# devBoard.net
KiCad netlist of a schematic drawn in Altium Designer
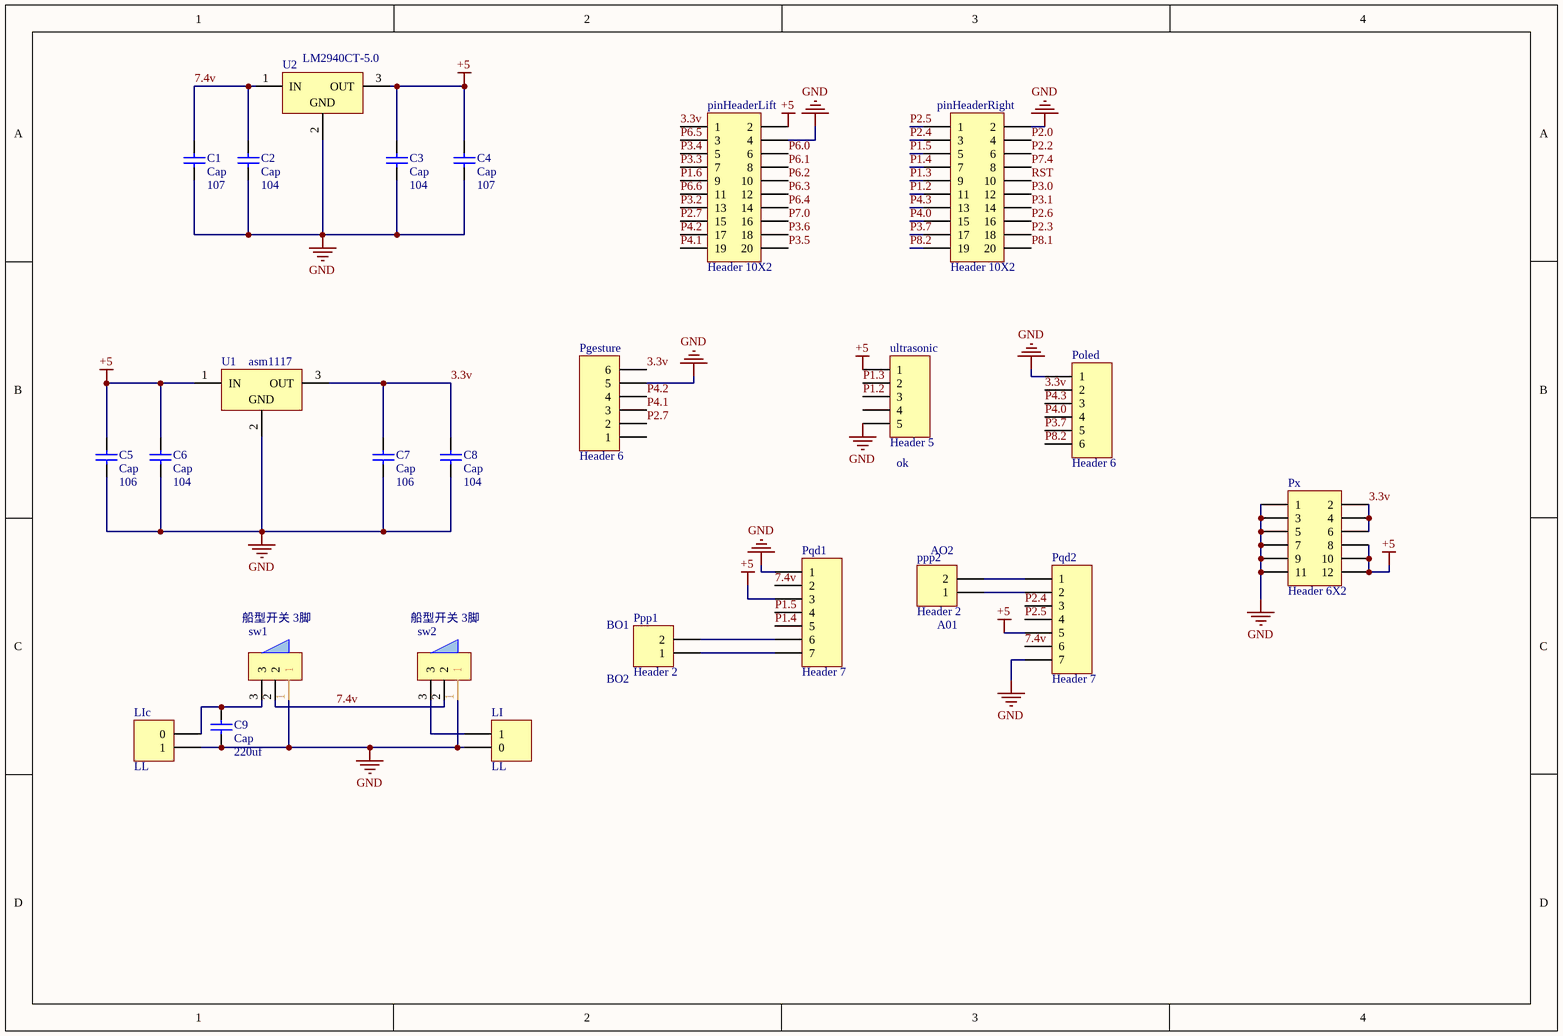
[diagram p0: devBoard.SchDoc]

(export (version "E")
  (design (tool "Eeschema 10.0.6"))
  (components
    (comp (ref "C1")
      (value "Cap")
      (footprint "RAD-0.3")
      (description "Capacitor")
      (fields (field (name "ALTIUM_VALUE") "107") (field (name "PUBLISHER") "Altium Limited"))
      (libsource (lib "Miscellaneous Devices") (part "Cap"))
    )
    (comp (ref "C2")
      (value "Cap")
      (footprint "RAD-0.3")
      (description "Capacitor")
      (fields (field (name "ALTIUM_VALUE") "104") (field (name "PUBLISHER") "Altium Limited"))
      (libsource (lib "Miscellaneous Devices") (part "Cap"))
    )
    (comp (ref "C3")
      (value "Cap")
      (footprint "RAD-0.3")
      (description "Capacitor")
      (fields (field (name "ALTIUM_VALUE") "104") (field (name "PUBLISHER") "Altium Limited"))
      (libsource (lib "Miscellaneous Devices") (part "Cap"))
    )
    (comp (ref "C4")
      (value "Cap")
      (footprint "RAD-0.3")
      (description "Capacitor")
      (fields (field (name "ALTIUM_VALUE") "107") (field (name "PUBLISHER") "Altium Limited"))
      (libsource (lib "Miscellaneous Devices") (part "Cap"))
    )
    (comp (ref "C5")
      (value "Cap")
      (footprint "RAD-0.3")
      (description "Capacitor")
      (fields (field (name "ALTIUM_VALUE") "106") (field (name "PUBLISHER") "Altium Limited"))
      (libsource (lib "Miscellaneous Devices") (part "Cap"))
    )
    (comp (ref "C6")
      (value "Cap")
      (footprint "RAD-0.3")
      (description "Capacitor")
      (fields (field (name "ALTIUM_VALUE") "104") (field (name "PUBLISHER") "Altium Limited"))
      (libsource (lib "Miscellaneous Devices") (part "Cap"))
    )
    (comp (ref "C7")
      (value "Cap")
      (footprint "RAD-0.3")
      (description "Capacitor")
      (fields (field (name "ALTIUM_VALUE") "106") (field (name "PUBLISHER") "Altium Limited"))
      (libsource (lib "Miscellaneous Devices") (part "Cap"))
    )
    (comp (ref "C8")
      (value "Cap")
      (footprint "RAD-0.3")
      (description "Capacitor")
      (fields (field (name "ALTIUM_VALUE") "104") (field (name "PUBLISHER") "Altium Limited"))
      (libsource (lib "Miscellaneous Devices") (part "Cap"))
    )
    (comp (ref "C9")
      (value "Cap")
      (footprint "RAD-0.3")
      (description "Capacitor")
      (fields (field (name "ALTIUM_VALUE") "220uf") (field (name "PUBLISHER") "Altium Limited"))
      (libsource (lib "Miscellaneous Devices") (part "Cap"))
    )
    (comp (ref "LI")
      (value "LL")
      (footprint "Con 2接线端子")
      (description "Header, 2-Pin")
      (fields (field (name "PUBLISHER") "Altium Limited"))
      (libsource (lib "") (part "Header 2_2"))
    )
    (comp (ref "LIc")
      (value "LL")
      (footprint "Con 2接线端子")
      (description "Header, 2-Pin")
      (fields (field (name "PUBLISHER") "Altium Limited"))
      (libsource (lib "Miscellaneous Connectors") (part "Header 2"))
    )
    (comp (ref "Pgesture")
      (value "Header 6")
      (footprint "HDR1X6")
      (description "Header, 6-Pin")
      (fields (field (name "PUBLISHER") "Altium Limited"))
      (libsource (lib "") (part "Header 6_1"))
    )
    (comp (ref "pinHeaderLift")
      (value "Header 10X2")
      (footprint "HDR2X10")
      (description "Header, 10-Pin, Dual row")
      (fields (field (name "PUBLISHER") "Altium Limited"))
      (libsource (lib "Miscellaneous Connectors") (part "Header 10X2"))
    )
    (comp (ref "pinHeaderRight")
      (value "Header 10X2")
      (footprint "HDR2X10")
      (description "Header, 10-Pin, Dual row")
      (fields (field (name "PUBLISHER") "Altium Limited"))
      (libsource (lib "Miscellaneous Connectors") (part "Header 10X2"))
    )
    (comp (ref "Poled")
      (value "Header 6")
      (footprint "HDR1X6")
      (description "Header, 6-Pin")
      (fields (field (name "PUBLISHER") "Altium Limited"))
      (libsource (lib "Miscellaneous Connectors") (part "Header 6"))
    )
    (comp (ref "Ppp1")
      (value "Header 2")
      (footprint "HDR1X2")
      (description "Header, 2-Pin")
      (fields (field (name "PUBLISHER") "Altium Limited"))
      (libsource (lib "") (part "Header 2_1"))
    )
    (comp (ref "ppp2")
      (value "Header 2")
      (footprint "HDR1X2")
      (description "Header, 2-Pin")
      (fields (field (name "PUBLISHER") "Altium Limited"))
      (libsource (lib "") (part "Header 2_1"))
    )
    (comp (ref "Pqd1")
      (value "Header 7")
      (footprint "HDR1X7")
      (description "Header, 7-Pin")
      (fields (field (name "PUBLISHER") "Altium Limited"))
      (libsource (lib "Miscellaneous Connectors") (part "Header 7"))
    )
    (comp (ref "Pqd2")
      (value "Header 7")
      (footprint "HDR1X7")
      (description "Header, 7-Pin")
      (fields (field (name "PUBLISHER") "Altium Limited"))
      (libsource (lib "Miscellaneous Connectors") (part "Header 7"))
    )
    (comp (ref "Px")
      (value "Header 6X2")
      (footprint "HDR2X6")
      (description "Header, 6-Pin, Dual row")
      (fields (field (name "PUBLISHER") "Altium Limited"))
      (libsource (lib "Miscellaneous Connectors") (part "Header 6X2"))
    )
    (comp (ref "sw1")
      (value "船型开关 3脚")
      (footprint "船型开关 3脚")
      (libsource (lib "altium-import") (part "root_0_船型开关 3脚_"))
    )
    (comp (ref "sw2")
      (value "船型开关 3脚")
      (footprint "船型开关 3脚")
      (libsource (lib "altium-import") (part "root_0_船型开关 3脚_"))
    )
    (comp (ref "U1")
      (value "asm1117")
      (footprint "T03B")
      (description "1A 5V")
      (fields (field (name "PUBLISHER") "Altium Limited"))
      (libsource (lib "TSLone") (part "LM2940CT-5.0"))
    )
    (comp (ref "U2")
      (value "LM2940CT-5.0")
      (footprint "T03B")
      (description "1A 5V")
      (fields (field (name "PUBLISHER") "Altium Limited"))
      (libsource (lib "TSLone") (part "LM2940CT-5.0"))
    )
    (comp (ref "ultrasonic")
      (value "Header 5")
      (footprint "HDR1X5")
      (description "Header, 5-Pin")
      (fields (field (name "PUBLISHER") "Altium Limited"))
      (libsource (lib "Miscellaneous Connectors") (part "Header 5"))
    )
  )
  (nets
    (net (code "1") (name "+5") (class "Default")
      (node (ref "C3") (pin "2") (pinfunction "2_2") (pintype "passive"))
      (node (ref "C4") (pin "2") (pinfunction "2_2") (pintype "passive"))
      (node (ref "C5") (pin "2") (pinfunction "2_2") (pintype "passive"))
      (node (ref "C6") (pin "2") (pinfunction "2_2") (pintype "passive"))
      (node (ref "Pqd1") (pin "3") (pinfunction "3_3") (pintype "passive"))
      (node (ref "Pqd2") (pin "5") (pinfunction "5_5") (pintype "passive"))
      (node (ref "Px") (pin "10") (pinfunction "10_10") (pintype "passive"))
      (node (ref "Px") (pin "12") (pinfunction "12_12") (pintype "passive"))
      (node (ref "Px") (pin "8") (pinfunction "8_8") (pintype "passive"))
      (node (ref "U1") (pin "1") (pinfunction "IN_1") (pintype "power_in"))
      (node (ref "U2") (pin "3") (pinfunction "OUT_3") (pintype "power_in"))
      (node (ref "pinHeaderLift") (pin "2") (pinfunction "2_2") (pintype "passive"))
      (node (ref "ultrasonic") (pin "1") (pinfunction "1_1") (pintype "passive"))
    )
    (net (code "2") (name "/3.3v") (class "Default")
      (node (ref "C7") (pin "2") (pinfunction "2_2") (pintype "passive"))
      (node (ref "C8") (pin "2") (pinfunction "2_2") (pintype "passive"))
      (node (ref "Pgesture") (pin "6") (pinfunction "6_6") (pintype "passive"))
      (node (ref "Poled") (pin "2") (pinfunction "2_2") (pintype "passive"))
      (node (ref "Px") (pin "2") (pinfunction "2_2") (pintype "passive"))
      (node (ref "Px") (pin "4") (pinfunction "4_4") (pintype "passive"))
      (node (ref "Px") (pin "6") (pinfunction "6_6") (pintype "passive"))
      (node (ref "U1") (pin "3") (pinfunction "OUT_3") (pintype "power_in"))
      (node (ref "pinHeaderLift") (pin "1") (pinfunction "1_1") (pintype "passive"))
    )
    (net (code "3") (name "/7.4v") (class "Default")
      (node (ref "C1") (pin "2") (pinfunction "2_2") (pintype "passive"))
      (node (ref "C2") (pin "2") (pinfunction "2_2") (pintype "passive"))
      (node (ref "Pqd1") (pin "2") (pinfunction "2_2") (pintype "passive"))
      (node (ref "Pqd2") (pin "6") (pinfunction "6_6") (pintype "passive"))
      (node (ref "U2") (pin "1") (pinfunction "IN_1") (pintype "power_in"))
      (node (ref "sw1") (pin "2") (pinfunction "2_2") (pintype "passive"))
      (node (ref "sw2") (pin "2") (pinfunction "2_2") (pintype "passive"))
    )
    (net (code "4") (name "/P1.2") (class "Default")
      (node (ref "pinHeaderRight") (pin "11") (pinfunction "11_11") (pintype "passive"))
      (node (ref "ultrasonic") (pin "3") (pinfunction "3_3") (pintype "passive"))
    )
    (net (code "5") (name "/P1.3") (class "Default")
      (node (ref "pinHeaderRight") (pin "9") (pinfunction "9_9") (pintype "passive"))
      (node (ref "ultrasonic") (pin "2") (pinfunction "2_2") (pintype "passive"))
    )
    (net (code "6") (name "/P1.4") (class "Default")
      (node (ref "Pqd1") (pin "5") (pinfunction "5_5") (pintype "passive"))
      (node (ref "pinHeaderRight") (pin "7") (pinfunction "7_7") (pintype "passive"))
    )
    (net (code "7") (name "/P1.5") (class "Default")
      (node (ref "Pqd1") (pin "4") (pinfunction "4_4") (pintype "passive"))
      (node (ref "pinHeaderRight") (pin "5") (pinfunction "5_5") (pintype "passive"))
    )
    (net (code "8") (name "/P1.6") (class "Default")
      (node (ref "pinHeaderLift") (pin "9") (pinfunction "9_9") (pintype "passive"))
    )
    (net (code "9") (name "/P2.0") (class "Default")
      (node (ref "pinHeaderRight") (pin "4") (pinfunction "4_4") (pintype "passive"))
    )
    (net (code "10") (name "/P2.2") (class "Default")
      (node (ref "pinHeaderRight") (pin "6") (pinfunction "6_6") (pintype "passive"))
    )
    (net (code "11") (name "/P2.3") (class "Default")
      (node (ref "pinHeaderRight") (pin "18") (pinfunction "18_18") (pintype "passive"))
    )
    (net (code "12") (name "/P2.4") (class "Default")
      (node (ref "Pqd2") (pin "3") (pinfunction "3_3") (pintype "passive"))
      (node (ref "pinHeaderRight") (pin "3") (pinfunction "3_3") (pintype "passive"))
    )
    (net (code "13") (name "/P2.5") (class "Default")
      (node (ref "Pqd2") (pin "4") (pinfunction "4_4") (pintype "passive"))
      (node (ref "pinHeaderRight") (pin "1") (pinfunction "1_1") (pintype "passive"))
    )
    (net (code "14") (name "/P2.6") (class "Default")
      (node (ref "pinHeaderRight") (pin "16") (pinfunction "16_16") (pintype "passive"))
    )
    (net (code "15") (name "/P2.7") (class "Default")
      (node (ref "Pgesture") (pin "2") (pinfunction "2_2") (pintype "passive"))
      (node (ref "pinHeaderLift") (pin "15") (pinfunction "15_15") (pintype "passive"))
    )
    (net (code "16") (name "/P3.0") (class "Default")
      (node (ref "pinHeaderRight") (pin "12") (pinfunction "12_12") (pintype "passive"))
    )
    (net (code "17") (name "/P3.1") (class "Default")
      (node (ref "pinHeaderRight") (pin "14") (pinfunction "14_14") (pintype "passive"))
    )
    (net (code "18") (name "/P3.2") (class "Default")
      (node (ref "pinHeaderLift") (pin "13") (pinfunction "13_13") (pintype "passive"))
    )
    (net (code "19") (name "/P3.3") (class "Default")
      (node (ref "pinHeaderLift") (pin "7") (pinfunction "7_7") (pintype "passive"))
    )
    (net (code "20") (name "/P3.4") (class "Default")
      (node (ref "pinHeaderLift") (pin "5") (pinfunction "5_5") (pintype "passive"))
    )
    (net (code "21") (name "/P3.5") (class "Default")
      (node (ref "pinHeaderLift") (pin "20") (pinfunction "20_20") (pintype "passive"))
    )
    (net (code "22") (name "/P3.6") (class "Default")
      (node (ref "pinHeaderLift") (pin "18") (pinfunction "18_18") (pintype "passive"))
    )
    (net (code "23") (name "/P3.7") (class "Default")
      (node (ref "Poled") (pin "5") (pinfunction "5_5") (pintype "passive"))
      (node (ref "pinHeaderRight") (pin "17") (pinfunction "17_17") (pintype "passive"))
    )
    (net (code "24") (name "/P4.0") (class "Default")
      (node (ref "Poled") (pin "4") (pinfunction "4_4") (pintype "passive"))
      (node (ref "pinHeaderRight") (pin "15") (pinfunction "15_15") (pintype "passive"))
    )
    (net (code "25") (name "/P4.1") (class "Default")
      (node (ref "Pgesture") (pin "3") (pinfunction "3_3") (pintype "passive"))
      (node (ref "pinHeaderLift") (pin "19") (pinfunction "19_19") (pintype "passive"))
    )
    (net (code "26") (name "/P4.2") (class "Default")
      (node (ref "Pgesture") (pin "4") (pinfunction "4_4") (pintype "passive"))
      (node (ref "pinHeaderLift") (pin "17") (pinfunction "17_17") (pintype "passive"))
    )
    (net (code "27") (name "/P4.3") (class "Default")
      (node (ref "Poled") (pin "3") (pinfunction "3_3") (pintype "passive"))
      (node (ref "pinHeaderRight") (pin "13") (pinfunction "13_13") (pintype "passive"))
    )
    (net (code "28") (name "/P6.0") (class "Default")
      (node (ref "pinHeaderLift") (pin "6") (pinfunction "6_6") (pintype "passive"))
    )
    (net (code "29") (name "/P6.1") (class "Default")
      (node (ref "pinHeaderLift") (pin "8") (pinfunction "8_8") (pintype "passive"))
    )
    (net (code "30") (name "/P6.2") (class "Default")
      (node (ref "pinHeaderLift") (pin "10") (pinfunction "10_10") (pintype "passive"))
    )
    (net (code "31") (name "/P6.3") (class "Default")
      (node (ref "pinHeaderLift") (pin "12") (pinfunction "12_12") (pintype "passive"))
    )
    (net (code "32") (name "/P6.4") (class "Default")
      (node (ref "pinHeaderLift") (pin "14") (pinfunction "14_14") (pintype "passive"))
    )
    (net (code "33") (name "/P6.5") (class "Default")
      (node (ref "pinHeaderLift") (pin "3") (pinfunction "3_3") (pintype "passive"))
    )
    (net (code "34") (name "/P6.6") (class "Default")
      (node (ref "pinHeaderLift") (pin "11") (pinfunction "11_11") (pintype "passive"))
    )
    (net (code "35") (name "/P7.0") (class "Default")
      (node (ref "pinHeaderLift") (pin "16") (pinfunction "16_16") (pintype "passive"))
    )
    (net (code "36") (name "/P7.4") (class "Default")
      (node (ref "pinHeaderRight") (pin "8") (pinfunction "8_8") (pintype "passive"))
    )
    (net (code "37") (name "/P8.1") (class "Default")
      (node (ref "pinHeaderRight") (pin "20") (pinfunction "20_20") (pintype "passive"))
    )
    (net (code "38") (name "/P8.2") (class "Default")
      (node (ref "Poled") (pin "6") (pinfunction "6_6") (pintype "passive"))
      (node (ref "pinHeaderRight") (pin "19") (pinfunction "19_19") (pintype "passive"))
    )
    (net (code "39") (name "/RST") (class "Default")
      (node (ref "pinHeaderRight") (pin "10") (pinfunction "10_10") (pintype "passive"))
    )
    (net (code "40") (name "GND") (class "Default")
      (node (ref "C1") (pin "1") (pinfunction "1_1") (pintype "passive"))
      (node (ref "C2") (pin "1") (pinfunction "1_1") (pintype "passive"))
      (node (ref "C3") (pin "1") (pinfunction "1_1") (pintype "passive"))
      (node (ref "C4") (pin "1") (pinfunction "1_1") (pintype "passive"))
      (node (ref "C5") (pin "1") (pinfunction "1_1") (pintype "passive"))
      (node (ref "C6") (pin "1") (pinfunction "1_1") (pintype "passive"))
      (node (ref "C7") (pin "1") (pinfunction "1_1") (pintype "passive"))
      (node (ref "C8") (pin "1") (pinfunction "1_1") (pintype "passive"))
      (node (ref "C9") (pin "1") (pinfunction "1_1") (pintype "passive"))
      (node (ref "LI") (pin "0") (pinfunction "0_0") (pintype "passive"))
      (node (ref "LIc") (pin "1") (pinfunction "1_1") (pintype "passive"))
      (node (ref "Pgesture") (pin "5") (pinfunction "5_5") (pintype "passive"))
      (node (ref "Poled") (pin "1") (pinfunction "1_1") (pintype "passive"))
      (node (ref "Pqd1") (pin "1") (pinfunction "1_1") (pintype "passive"))
      (node (ref "Pqd2") (pin "7") (pinfunction "7_7") (pintype "passive"))
      (node (ref "Px") (pin "1") (pinfunction "1_1") (pintype "passive"))
      (node (ref "Px") (pin "11") (pinfunction "11_11") (pintype "passive"))
      (node (ref "Px") (pin "3") (pinfunction "3_3") (pintype "passive"))
      (node (ref "Px") (pin "5") (pinfunction "5_5") (pintype "passive"))
      (node (ref "Px") (pin "7") (pinfunction "7_7") (pintype "passive"))
      (node (ref "Px") (pin "9") (pinfunction "9_9") (pintype "passive"))
      (node (ref "U1") (pin "2") (pinfunction "GND_2") (pintype "power_in"))
      (node (ref "U2") (pin "2") (pinfunction "GND_2") (pintype "power_in"))
      (node (ref "pinHeaderLift") (pin "4") (pinfunction "4_4") (pintype "passive"))
      (node (ref "pinHeaderRight") (pin "2") (pinfunction "2_2") (pintype "passive"))
      (node (ref "sw1") (pin "1") (pinfunction "1_1") (pintype "passive"))
      (node (ref "sw2") (pin "1") (pinfunction "1_1") (pintype "passive"))
      (node (ref "ultrasonic") (pin "5") (pinfunction "5_5") (pintype "passive"))
    )
    (net (code "41") (name "Net-(C9-Pad2)") (class "Default")
      (node (ref "C9") (pin "2") (pinfunction "2_2") (pintype "passive"))
      (node (ref "LIc") (pin "0") (pinfunction "0_0") (pintype "passive"))
      (node (ref "sw1") (pin "3") (pinfunction "3_3") (pintype "passive"))
    )
    (net (code "42") (name "Net-(LI-Pad1)") (class "Default")
      (node (ref "LI") (pin "1") (pinfunction "1_1") (pintype "passive"))
      (node (ref "sw2") (pin "3") (pinfunction "3_3") (pintype "passive"))
    )
    (net (code "43") (name "Net-(Ppp1-Pad1)") (class "Default")
      (node (ref "Ppp1") (pin "1") (pinfunction "1_1") (pintype "passive"))
      (node (ref "Pqd1") (pin "7") (pinfunction "7_7") (pintype "passive"))
    )
    (net (code "44") (name "Net-(Ppp1-Pad2)") (class "Default")
      (node (ref "Ppp1") (pin "2") (pinfunction "2_2") (pintype "passive"))
      (node (ref "Pqd1") (pin "6") (pinfunction "6_6") (pintype "passive"))
    )
    (net (code "45") (name "Net-(Pqd2-Pad1)") (class "Default")
      (node (ref "Pqd2") (pin "1") (pinfunction "1_1") (pintype "passive"))
      (node (ref "ppp2") (pin "2") (pinfunction "2_2") (pintype "passive"))
    )
    (net (code "46") (name "Net-(Pqd2-Pad2)") (class "Default")
      (node (ref "Pqd2") (pin "2") (pinfunction "2_2") (pintype "passive"))
      (node (ref "ppp2") (pin "1") (pinfunction "1_1") (pintype "passive"))
    )
    (net (code "47") (name "unconnected-(Pgesture-Pad1)") (class "Default")
      (node (ref "Pgesture") (pin "1") (pinfunction "1_1") (pintype "passive"))
    )
    (net (code "48") (name "unconnected-(ultrasonic-Pad4)") (class "Default")
      (node (ref "ultrasonic") (pin "4") (pinfunction "4_4") (pintype "passive"))
    )
  )
)
